# Works_007_b.net
KiCad netlist of a schematic drawn in EAGLE
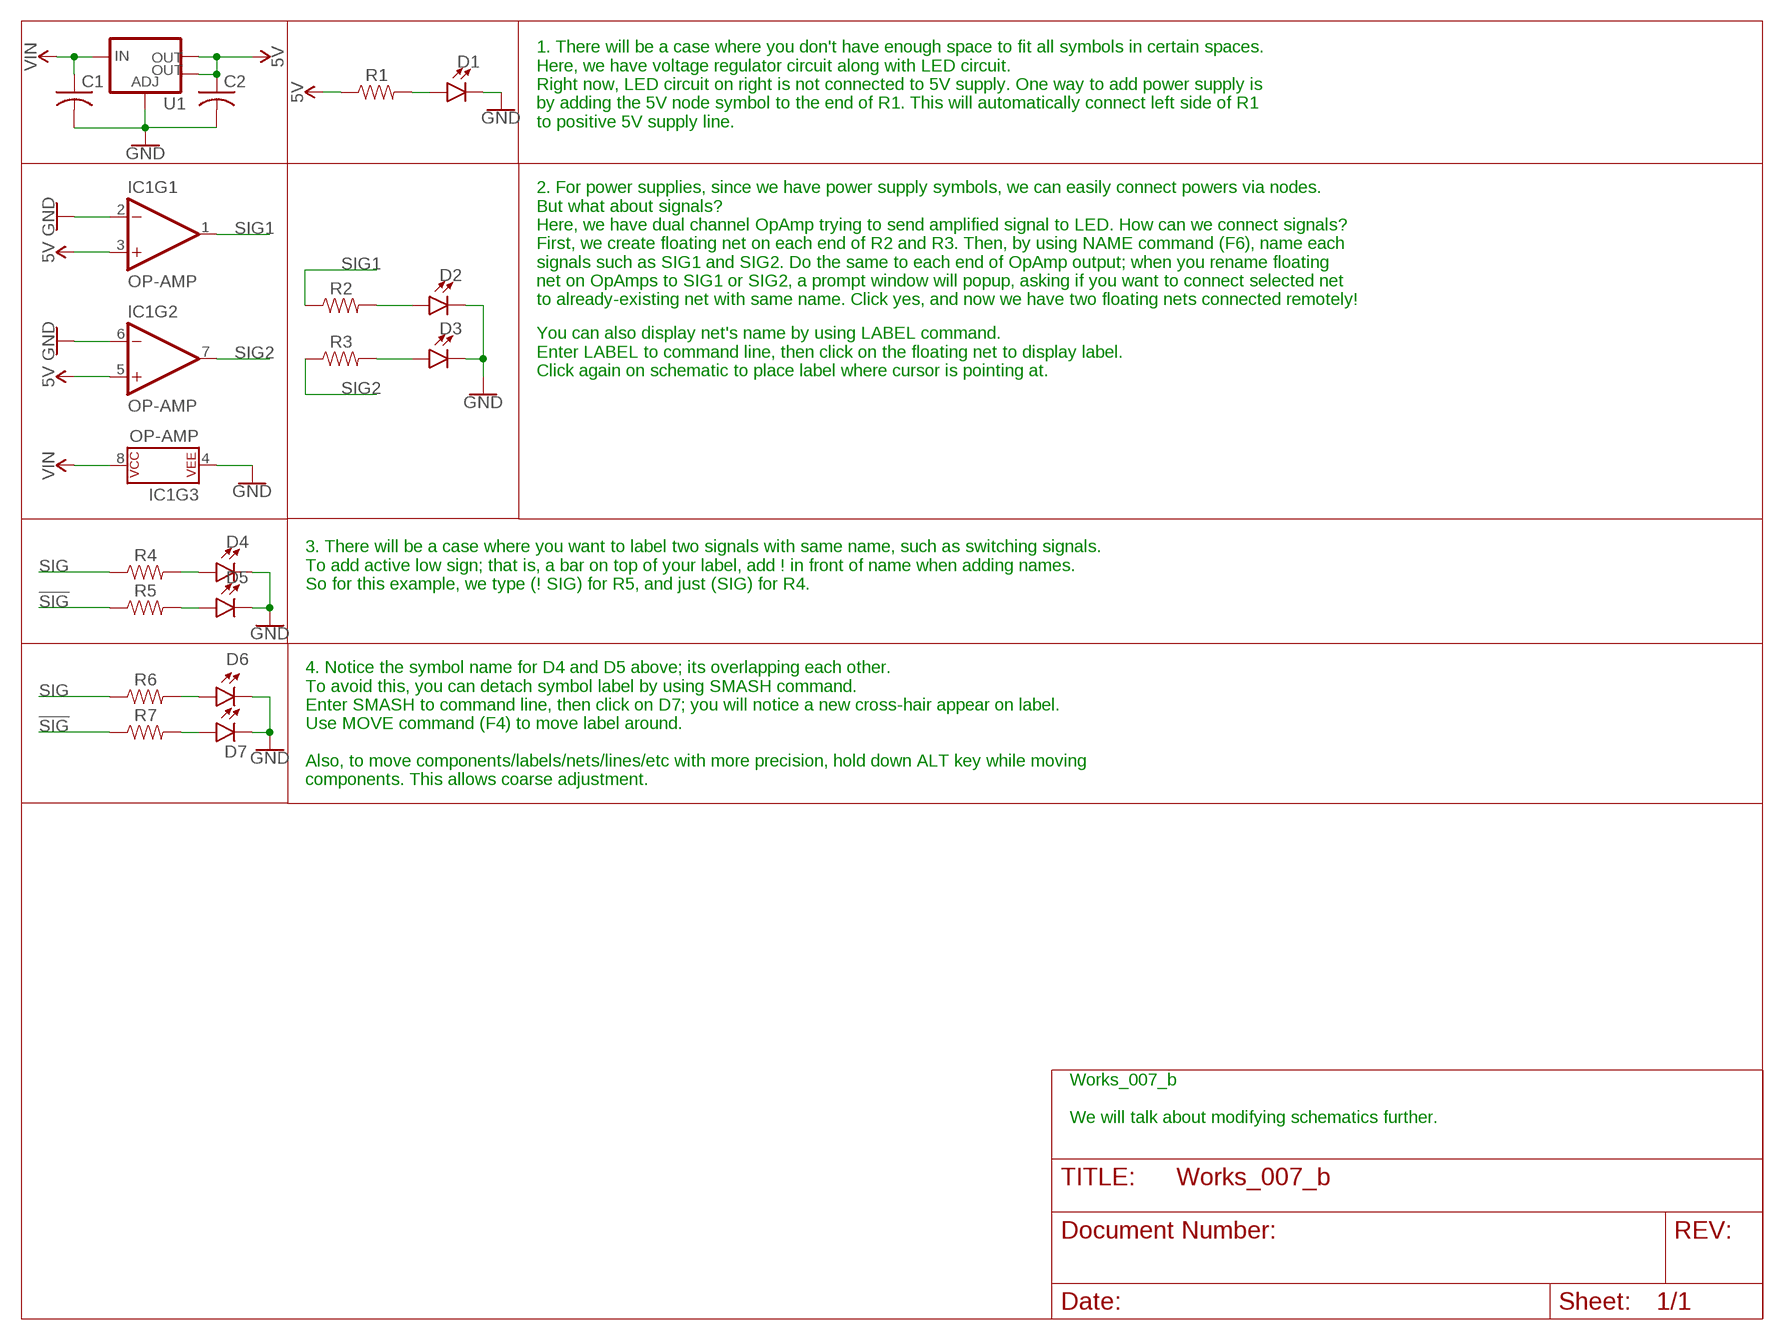
[diagram p0: schematic, sheet 1]

(export (version "E")
  (design (tool "Eeschema 10.0.6"))
  (components
    (comp (ref "C1")
      (value "C-USC0805")
      (footprint "eagle-import:C0805")
      (libsource (lib "eagle-import") (part "C-USC0805"))
    )
    (comp (ref "C2")
      (value "C-USC0805")
      (footprint "eagle-import:C0805")
      (libsource (lib "eagle-import") (part "C-USC0805"))
    )
    (comp (ref "D1")
      (value "LED5MM")
      (footprint "eagle-import:LED_5MM")
      (libsource (lib "eagle-import") (part "LED5MM"))
    )
    (comp (ref "D2")
      (value "LED5MM")
      (footprint "eagle-import:LED_5MM")
      (libsource (lib "eagle-import") (part "LED5MM"))
    )
    (comp (ref "D3")
      (value "LED5MM")
      (footprint "eagle-import:LED_5MM")
      (libsource (lib "eagle-import") (part "LED5MM"))
    )
    (comp (ref "D4")
      (value "LED5MM")
      (footprint "eagle-import:LED_5MM")
      (libsource (lib "eagle-import") (part "LED5MM"))
    )
    (comp (ref "D5")
      (value "LED5MM")
      (footprint "eagle-import:LED_5MM")
      (libsource (lib "eagle-import") (part "LED5MM"))
    )
    (comp (ref "D6")
      (value "LED5MM")
      (footprint "eagle-import:LED_5MM")
      (libsource (lib "eagle-import") (part "LED5MM"))
    )
    (comp (ref "D7")
      (value "LED5MM")
      (footprint "eagle-import:LED_5MM")
      (libsource (lib "eagle-import") (part "LED5MM"))
    )
    (comp (ref "IC1")
      (value "OP-AMP")
      (footprint "eagle-import:DIP08")
      (libsource (lib "eagle-import") (part "OPAMP-DUALDIP"))
    )
    (comp (ref "R1")
      (value "RESISTOR0805")
      (footprint "eagle-import:0805")
      (libsource (lib "eagle-import") (part "RESISTOR0805"))
    )
    (comp (ref "R2")
      (value "RESISTOR0805")
      (footprint "eagle-import:0805")
      (libsource (lib "eagle-import") (part "RESISTOR0805"))
    )
    (comp (ref "R3")
      (value "RESISTOR0805")
      (footprint "eagle-import:0805")
      (libsource (lib "eagle-import") (part "RESISTOR0805"))
    )
    (comp (ref "R4")
      (value "RESISTOR0805")
      (footprint "eagle-import:0805")
      (libsource (lib "eagle-import") (part "RESISTOR0805"))
    )
    (comp (ref "R5")
      (value "RESISTOR0805")
      (footprint "eagle-import:0805")
      (libsource (lib "eagle-import") (part "RESISTOR0805"))
    )
    (comp (ref "R6")
      (value "RESISTOR0805")
      (footprint "eagle-import:0805")
      (libsource (lib "eagle-import") (part "RESISTOR0805"))
    )
    (comp (ref "R7")
      (value "RESISTOR0805")
      (footprint "eagle-import:0805")
      (libsource (lib "eagle-import") (part "RESISTOR0805"))
    )
    (comp (ref "U1")
      (value "V_REG_LM1117SOT223")
      (footprint "eagle-import:SOT223")
      (libsource (lib "eagle-import") (part "V_REG_LM1117SOT223"))
    )
  )
  (nets
    (net (code "1") (name "/SIG") (class "Default")
      (node (ref "R4") (pin "1") (pinfunction "1_1") (pintype "passive"))
      (node (ref "R6") (pin "1") (pinfunction "1_1") (pintype "passive"))
    )
    (net (code "2") (name "/SIG1") (class "Default")
      (node (ref "IC1") (pin "1") (pinfunction "OUT_1") (pintype "output"))
      (node (ref "R2") (pin "1") (pinfunction "1_1") (pintype "passive"))
    )
    (net (code "3") (name "/SIG2") (class "Default")
      (node (ref "IC1") (pin "7") (pinfunction "OUT_7") (pintype "output"))
      (node (ref "R3") (pin "1") (pinfunction "1_1") (pintype "passive"))
    )
    (net (code "4") (name "/~{SIG}") (class "Default")
      (node (ref "R5") (pin "1") (pinfunction "1_1") (pintype "passive"))
      (node (ref "R7") (pin "1") (pinfunction "1_1") (pintype "passive"))
    )
    (net (code "5") (name "5V") (class "Default")
      (node (ref "C2") (pin "1") (pinfunction "1_1") (pintype "passive"))
      (node (ref "IC1") (pin "3") (pinfunction "+IN_3") (pintype "input"))
      (node (ref "IC1") (pin "5") (pinfunction "+IN_5") (pintype "input"))
      (node (ref "R1") (pin "1") (pinfunction "1_1") (pintype "passive"))
      (node (ref "U1") (pin "2") (pinfunction "OUT_2") (pintype "output"))
      (node (ref "U1") (pin "4") (pinfunction "OUT_4") (pintype "output"))
    )
    (net (code "6") (name "GND") (class "Default")
      (node (ref "C1") (pin "2") (pinfunction "2_2") (pintype "passive"))
      (node (ref "C2") (pin "2") (pinfunction "2_2") (pintype "passive"))
      (node (ref "D1") (pin "K") (pinfunction "C_K") (pintype "passive"))
      (node (ref "D2") (pin "K") (pinfunction "C_K") (pintype "passive"))
      (node (ref "D3") (pin "K") (pinfunction "C_K") (pintype "passive"))
      (node (ref "D4") (pin "K") (pinfunction "C_K") (pintype "passive"))
      (node (ref "D5") (pin "K") (pinfunction "C_K") (pintype "passive"))
      (node (ref "D6") (pin "K") (pinfunction "C_K") (pintype "passive"))
      (node (ref "D7") (pin "K") (pinfunction "C_K") (pintype "passive"))
      (node (ref "IC1") (pin "2") (pinfunction "-IN_2") (pintype "input"))
      (node (ref "IC1") (pin "4") (pinfunction "P$V-_4") (pintype "bidirectional"))
      (node (ref "IC1") (pin "6") (pinfunction "-IN_6") (pintype "input"))
      (node (ref "U1") (pin "1") (pinfunction "ADJ_1") (pintype "input"))
    )
    (net (code "7") (name "Net-(D1-PadA)") (class "Default")
      (node (ref "D1") (pin "A") (pinfunction "A_A") (pintype "passive"))
      (node (ref "R1") (pin "2") (pinfunction "2_2") (pintype "passive"))
    )
    (net (code "8") (name "Net-(D2-PadA)") (class "Default")
      (node (ref "D2") (pin "A") (pinfunction "A_A") (pintype "passive"))
      (node (ref "R2") (pin "2") (pinfunction "2_2") (pintype "passive"))
    )
    (net (code "9") (name "Net-(D3-PadA)") (class "Default")
      (node (ref "D3") (pin "A") (pinfunction "A_A") (pintype "passive"))
      (node (ref "R3") (pin "2") (pinfunction "2_2") (pintype "passive"))
    )
    (net (code "10") (name "Net-(D4-PadA)") (class "Default")
      (node (ref "D4") (pin "A") (pinfunction "A_A") (pintype "passive"))
      (node (ref "R4") (pin "2") (pinfunction "2_2") (pintype "passive"))
    )
    (net (code "11") (name "Net-(D5-PadA)") (class "Default")
      (node (ref "D5") (pin "A") (pinfunction "A_A") (pintype "passive"))
      (node (ref "R5") (pin "2") (pinfunction "2_2") (pintype "passive"))
    )
    (net (code "12") (name "Net-(D6-PadA)") (class "Default")
      (node (ref "D6") (pin "A") (pinfunction "A_A") (pintype "passive"))
      (node (ref "R6") (pin "2") (pinfunction "2_2") (pintype "passive"))
    )
    (net (code "13") (name "Net-(D7-PadA)") (class "Default")
      (node (ref "D7") (pin "A") (pinfunction "A_A") (pintype "passive"))
      (node (ref "R7") (pin "2") (pinfunction "2_2") (pintype "passive"))
    )
    (net (code "14") (name "VIN") (class "Default")
      (node (ref "C1") (pin "1") (pinfunction "1_1") (pintype "passive"))
      (node (ref "IC1") (pin "8") (pinfunction "P$V+_8") (pintype "bidirectional"))
      (node (ref "U1") (pin "3") (pinfunction "IN_3") (pintype "input"))
    )
  )
)
